# B293A_CoX_Amp_with_Programmable_Gain.net
KiCad netlist of a schematic drawn in Altium Designer
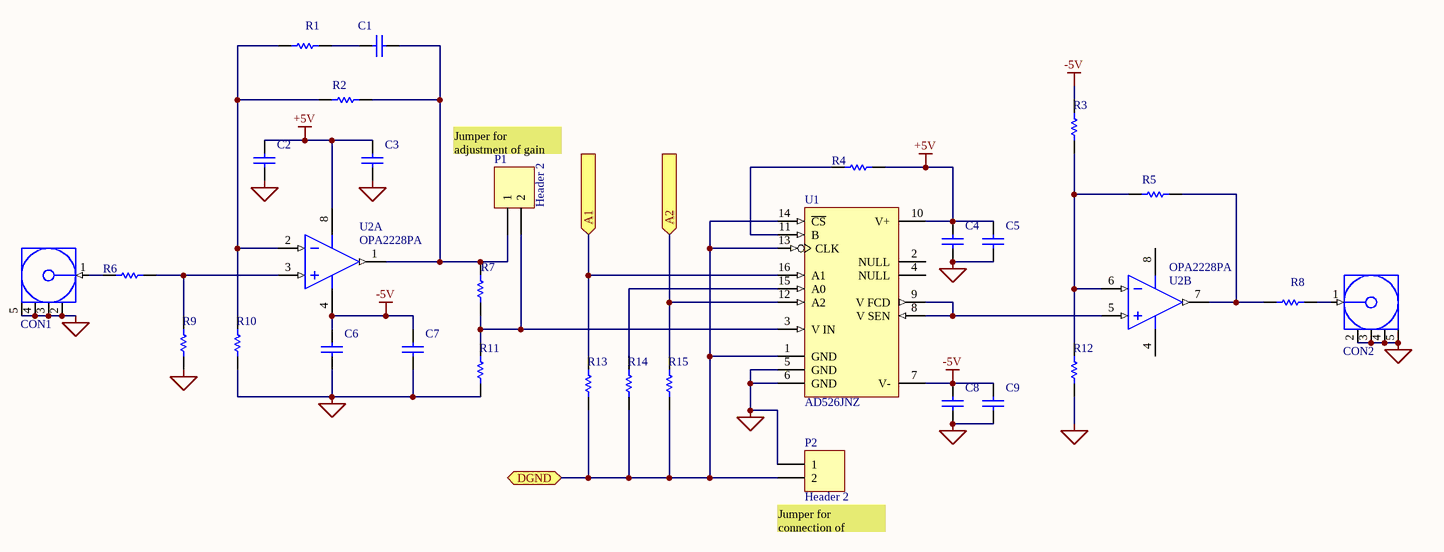
[diagram p0: B293A CoX Amp with Programmable Gain.SchDoc]

(export (version "E")
  (design (tool "Eeschema 10.0.6"))
  (components
    (comp (ref "C1")
      (value "CAP 47pF 50V 1206(3216)")
      (footprint "CAPC1206(3216)170_M")
      (description "CAP 47pF 50V ±10% 1206 (3216 Metric) Thickness 1.7mm SMD")
      (fields (field (name "TOLERANCE") "±10%"))
      (libsource (lib "Altium Content Vault") (part "CAP"))
    )
    (comp (ref "C2")
      (value "CAP 10uF 50V 1206(3216)")
      (footprint "CAPC1206(3216)190_M")
      (description "CAP 10uF 50V ±10% 1206 (3216 Metric) Thickness 1.9mm SMD")
      (fields (field (name "TOLERANCE") "±10%"))
      (libsource (lib "Altium Content Vault") (part "CAP"))
    )
    (comp (ref "C3")
      (value "CAP 10nF 50V 1206(3216)")
      (footprint "CAPC1206(3216)170_M")
      (description "CAP 10nF 50V ±10% 1206 (3216 Metric) Thickness 1.7mm SMD")
      (fields (field (name "TOLERANCE") "±10%"))
      (libsource (lib "Altium Content Vault") (part "CAP"))
    )
    (comp (ref "C4")
      (value "CAP 10nF 50V 1206(3216)")
      (footprint "CAPC1206(3216)170_M")
      (description "CAP 10nF 50V ±10% 1206 (3216 Metric) Thickness 1.7mm SMD")
      (fields (field (name "TOLERANCE") "±10%"))
      (libsource (lib "Altium Content Vault") (part "CAP"))
    )
    (comp (ref "C5")
      (value "CAP 10uF 50V 1206(3216)")
      (footprint "CAPC1206(3216)190_M")
      (description "CAP 10uF 50V ±10% 1206 (3216 Metric) Thickness 1.9mm SMD")
      (fields (field (name "TOLERANCE") "±10%"))
      (libsource (lib "Altium Content Vault") (part "CAP"))
    )
    (comp (ref "C6")
      (value "CAP 10nF 50V 1206(3216)")
      (footprint "CAPC1206(3216)170_M")
      (description "CAP 10nF 50V ±10% 1206 (3216 Metric) Thickness 1.7mm SMD")
      (fields (field (name "TOLERANCE") "±10%"))
      (libsource (lib "Altium Content Vault") (part "CAP"))
    )
    (comp (ref "C7")
      (value "CAP 10uF 50V 1206(3216)")
      (footprint "CAPC1206(3216)190_M")
      (description "CAP 10uF 50V ±10% 1206 (3216 Metric) Thickness 1.9mm SMD")
      (fields (field (name "TOLERANCE") "±10%"))
      (libsource (lib "Altium Content Vault") (part "CAP"))
    )
    (comp (ref "C8")
      (value "CAP 10nF 50V 1206(3216)")
      (footprint "CAPC1206(3216)170_M")
      (description "CAP 10nF 50V ±10% 1206 (3216 Metric) Thickness 1.7mm SMD")
      (fields (field (name "TOLERANCE") "±10%"))
      (libsource (lib "Altium Content Vault") (part "CAP"))
    )
    (comp (ref "C9")
      (value "CAP 10uF 50V 1206(3216)")
      (footprint "CAPC1206(3216)190_M")
      (description "CAP 10uF 50V ±10% 1206 (3216 Metric) Thickness 1.9mm SMD")
      (fields (field (name "TOLERANCE") "±10%"))
      (libsource (lib "Altium Content Vault") (part "CAP"))
    )
    (comp (ref "CON1")
      (value "SMA Vertical")
      (footprint "Matt PCB Library:SMA Vertical")
      (fields (field (name "MANUFACTURERS PART NO") "5-1814832-1"))
      (libsource (lib "Matt SCH Library") (part "SMA Vertical"))
    )
    (comp (ref "CON2")
      (value "SMA Vertical")
      (footprint "Matt PCB Library:SMA Vertical")
      (fields (field (name "MANUFACTURERS PART NO") "5-1814832-1"))
      (libsource (lib "Matt SCH Library") (part "SMA Vertical"))
    )
    (comp (ref "P1")
      (value "Header 2")
      (footprint "HDR1X2")
      (description "Header, 2-Pin")
      (fields (field (name "PUBLISHER") "Altium Limited"))
      (libsource (lib "") (part "Header 2_1"))
    )
    (comp (ref "P2")
      (value "Header 2")
      (footprint "HDR1X2")
      (description "Header, 2-Pin")
      (fields (field (name "PUBLISHER") "Altium Limited"))
      (libsource (lib "Miscellaneous Connectors") (part "Header 2"))
    )
    (comp (ref "R1")
      (value "1K5 1% 1206(3216)")
      (footprint "RESC1206(3216)_L")
      (description "1K5 0.25W 1% 1206 (3216 Metric)  SMD")
      (fields (field (name "TOLERANCE") "1 %"))
      (libsource (lib "Altium Content Vault") (part "RES"))
    )
    (comp (ref "R2")
      (value "100K 1% 1206(3216)")
      (footprint "RESC1206(3216)_L")
      (description "100K 0.25W 1% 1206 (3216 Metric)  SMD")
      (fields (field (name "TOLERANCE") "1 %"))
      (libsource (lib "Altium Content Vault") (part "RES"))
    )
    (comp (ref "R3")
      (value "150K 1% 1206(3216)")
      (footprint "RESC1206(3216)_L")
      (description "150K 0.25W 1% 1206 (3216 Metric)  SMD")
      (fields (field (name "TOLERANCE") "1 %"))
      (libsource (lib "Altium Content Vault") (part "RES"))
    )
    (comp (ref "R4")
      (value "10K 1% 1206(3216)")
      (footprint "RESC1206(3216)_L")
      (description "10K 0.25W 1% 1206 (3216 Metric)  SMD")
      (fields (field (name "TOLERANCE") "1 %"))
      (libsource (lib "Altium Content Vault") (part "RES"))
    )
    (comp (ref "R5")
      (value "10K 1% 1206(3216)")
      (footprint "RESC1206(3216)_L")
      (description "10K 0.25W 1% 1206 (3216 Metric)  SMD")
      (fields (field (name "TOLERANCE") "1 %"))
      (libsource (lib "Altium Content Vault") (part "RES"))
    )
    (comp (ref "R6")
      (value "100R 1% 1206(3216)")
      (footprint "RESC1206(3216)_N")
      (description "100R 0.25W 1% 1206 (3216 Metric)  SMD")
      (fields (field (name "TOLERANCE") "1 %"))
      (libsource (lib "Altium Content Vault") (part "RES"))
    )
    (comp (ref "R7")
      (value "10K 1% 1206(3216)")
      (footprint "RESC1206(3216)_L")
      (description "10K 0.25W 1% 1206 (3216 Metric)  SMD")
      (fields (field (name "TOLERANCE") "1 %"))
      (libsource (lib "Altium Content Vault") (part "RES"))
    )
    (comp (ref "R8")
      (value "100R 1% 1206(3216)")
      (footprint "RESC1206(3216)_N")
      (description "100R 0.25W 1% 1206 (3216 Metric)  SMD")
      (fields (field (name "TOLERANCE") "1 %"))
      (libsource (lib "Altium Content Vault") (part "RES"))
    )
    (comp (ref "R9")
      (value "27K 1% 1206(3216)")
      (footprint "RESC1206(3216)_M")
      (description "27K 0.25W 1% 1206 (3216 Metric)  SMD")
      (fields (field (name "TOLERANCE") "1 %"))
      (libsource (lib "Altium Content Vault") (part "RES"))
    )
    (comp (ref "R10")
      (value "330R 1% 1206(3216)")
      (footprint "RESC1206(3216)_M")
      (description "330R 0.25W 1% 1206 (3216 Metric)  SMD")
      (fields (field (name "TOLERANCE") "1 %"))
      (libsource (lib "Altium Content Vault") (part "RES"))
    )
    (comp (ref "R11")
      (value "1K2 1% 1206(3216)")
      (footprint "RESC1206(3216)_M")
      (description "1K2 0.25W 1% 1206 (3216 Metric)  SMD")
      (fields (field (name "TOLERANCE") "1 %"))
      (libsource (lib "Altium Content Vault") (part "CMP-1014-00518-1"))
    )
    (comp (ref "R12")
      (value "1K2 1% 1206(3216)")
      (footprint "RESC1206(3216)_M")
      (description "1K2 0.25W 1% 1206 (3216 Metric)  SMD")
      (fields (field (name "TOLERANCE") "1 %"))
      (libsource (lib "Altium Content Vault") (part "RES"))
    )
    (comp (ref "R13")
      (value "10K 1% 1206(3216)")
      (footprint "RESC1206(3216)_L")
      (description "10K 0.25W 1% 1206 (3216 Metric)  SMD")
      (fields (field (name "TOLERANCE") "1 %"))
      (libsource (lib "Altium Content Vault") (part "RES"))
    )
    (comp (ref "R14")
      (value "10K 1% 1206(3216)")
      (footprint "RESC1206(3216)_L")
      (description "10K 0.25W 1% 1206 (3216 Metric)  SMD")
      (fields (field (name "TOLERANCE") "1 %"))
      (libsource (lib "Altium Content Vault") (part "RES"))
    )
    (comp (ref "R15")
      (value "10K 1% 1206(3216)")
      (footprint "RESC1206(3216)_L")
      (description "10K 0.25W 1% 1206 (3216 Metric)  SMD")
      (fields (field (name "TOLERANCE") "1 %"))
      (libsource (lib "Altium Content Vault") (part "RES"))
    )
    (comp (ref "U1")
      (value "AD526JNZ")
      (footprint "D-16_B")
      (description "Software Programmable Gain Amplifier")
      (fields (field (name "PUBLISHER") "Altium Limited"))
      (libsource (lib "AD Instrumentation Amplifier") (part "AD526AD"))
    )
    (comp (ref "U2")
      (value "OPA2228PA")
      (footprint "TI-P8")
      (fields (field (name "MANUFACTURER") "Texas Instruments"))
      (libsource (lib "Altium Content Vault") (part "TI-OPA-8_2"))
    )
  )
  (nets
    (net (code "1") (name "+5V") (class "Default")
      (node (ref "C2") (pin "2") (pinfunction "2_2") (pintype "passive"))
      (node (ref "C3") (pin "2") (pinfunction "2_2") (pintype "passive"))
      (node (ref "C4") (pin "2") (pinfunction "2_2") (pintype "passive"))
      (node (ref "C5") (pin "2") (pinfunction "2_2") (pintype "passive"))
      (node (ref "R4") (pin "1") (pinfunction "1_1") (pintype "passive"))
      (node (ref "U1") (pin "10") (pinfunction "V+_10") (pintype "power_in"))
      (node (ref "U2") (pin "8") (pinfunction "V+_8") (pintype "power_in"))
    )
    (net (code "2") (name "-5V") (class "Default")
      (node (ref "C6") (pin "2") (pinfunction "2_2") (pintype "passive"))
      (node (ref "C7") (pin "2") (pinfunction "2_2") (pintype "passive"))
      (node (ref "C8") (pin "2") (pinfunction "2_2") (pintype "passive"))
      (node (ref "C9") (pin "2") (pinfunction "2_2") (pintype "passive"))
      (node (ref "R3") (pin "2") (pinfunction "2_2") (pintype "passive"))
      (node (ref "U1") (pin "7") (pinfunction "V-_7") (pintype "power_in"))
      (node (ref "U2") (pin "4") (pinfunction "V-_4") (pintype "power_in"))
    )
    (net (code "3") (name "/A1") (class "Default")
      (node (ref "R13") (pin "2") (pinfunction "2_2") (pintype "passive"))
      (node (ref "U1") (pin "16") (pinfunction "A1_16") (pintype "input"))
    )
    (net (code "4") (name "/A2") (class "Default")
      (node (ref "R15") (pin "2") (pinfunction "2_2") (pintype "passive"))
      (node (ref "U1") (pin "12") (pinfunction "A2_12") (pintype "input"))
    )
    (net (code "5") (name "/DGND") (class "Default")
      (node (ref "P2") (pin "2") (pinfunction "2_2") (pintype "passive"))
      (node (ref "R13") (pin "1") (pinfunction "1_1") (pintype "passive"))
      (node (ref "R14") (pin "1") (pinfunction "1_1") (pintype "passive"))
      (node (ref "R15") (pin "1") (pinfunction "1_1") (pintype "passive"))
      (node (ref "U1") (pin "1") (pinfunction "GND_1") (pintype "power_in"))
      (node (ref "U1") (pin "13") (pinfunction "CLK_13") (pintype "input"))
      (node (ref "U1") (pin "14") (pinfunction "~{CS}_14") (pintype "input"))
    )
    (net (code "6") (name "GND") (class "Default")
      (node (ref "C2") (pin "1") (pinfunction "1_1") (pintype "passive"))
      (node (ref "C3") (pin "1") (pinfunction "1_1") (pintype "passive"))
      (node (ref "C4") (pin "1") (pinfunction "1_1") (pintype "passive"))
      (node (ref "C5") (pin "1") (pinfunction "1_1") (pintype "passive"))
      (node (ref "C6") (pin "1") (pinfunction "1_1") (pintype "passive"))
      (node (ref "C7") (pin "1") (pinfunction "1_1") (pintype "passive"))
      (node (ref "C8") (pin "1") (pinfunction "1_1") (pintype "passive"))
      (node (ref "C9") (pin "1") (pinfunction "1_1") (pintype "passive"))
      (node (ref "CON1") (pin "2") (pinfunction "GND_2") (pintype "power_in"))
      (node (ref "CON1") (pin "3") (pinfunction "GND_3") (pintype "power_in"))
      (node (ref "CON1") (pin "4") (pinfunction "GND_4") (pintype "power_in"))
      (node (ref "CON1") (pin "5") (pinfunction "GND_5") (pintype "power_in"))
      (node (ref "CON2") (pin "2") (pinfunction "GND_2") (pintype "power_in"))
      (node (ref "CON2") (pin "3") (pinfunction "GND_3") (pintype "power_in"))
      (node (ref "CON2") (pin "4") (pinfunction "GND_4") (pintype "power_in"))
      (node (ref "CON2") (pin "5") (pinfunction "GND_5") (pintype "power_in"))
      (node (ref "P2") (pin "1") (pinfunction "1_1") (pintype "passive"))
      (node (ref "R10") (pin "1") (pinfunction "1_1") (pintype "passive"))
      (node (ref "R11") (pin "1") (pinfunction "1_1") (pintype "passive"))
      (node (ref "R12") (pin "1") (pinfunction "1_1") (pintype "passive"))
      (node (ref "R9") (pin "1") (pinfunction "1_1") (pintype "passive"))
      (node (ref "U1") (pin "5") (pinfunction "GND_5") (pintype "power_in"))
      (node (ref "U1") (pin "6") (pinfunction "GND_6") (pintype "power_in"))
    )
    (net (code "7") (name "Net-(C1-Pad2)") (class "Default")
      (node (ref "C1") (pin "2") (pinfunction "2_2") (pintype "passive"))
      (node (ref "R1") (pin "2") (pinfunction "2_2") (pintype "passive"))
    )
    (net (code "8") (name "Net-(CON1-Signal)") (class "Default")
      (node (ref "CON1") (pin "1") (pinfunction "Signal_1") (pintype "input"))
      (node (ref "R6") (pin "2") (pinfunction "2_2") (pintype "passive"))
    )
    (net (code "9") (name "Net-(CON2-Signal)") (class "Default")
      (node (ref "CON2") (pin "1") (pinfunction "Signal_1") (pintype "input"))
      (node (ref "R8") (pin "2") (pinfunction "2_2") (pintype "passive"))
    )
    (net (code "10") (name "Net-(U1-A0)") (class "Default")
      (node (ref "R14") (pin "2") (pinfunction "2_2") (pintype "passive"))
      (node (ref "U1") (pin "15") (pinfunction "A0_15") (pintype "input"))
    )
    (net (code "11") (name "Net-(U1-B)") (class "Default")
      (node (ref "R4") (pin "2") (pinfunction "2_2") (pintype "passive"))
      (node (ref "U1") (pin "11") (pinfunction "B_11") (pintype "input"))
    )
    (net (code "12") (name "Net-(U1-V_FCD)") (class "Default")
      (node (ref "U1") (pin "8") (pinfunction "V_SEN_8") (pintype "input"))
      (node (ref "U1") (pin "9") (pinfunction "V_FCD_9") (pintype "output"))
      (node (ref "U2") (pin "5") (pinfunction "IN_B+_5") (pintype "input"))
    )
    (net (code "13") (name "Net-(U1-V_IN)") (class "Default")
      (node (ref "P1") (pin "2") (pinfunction "2_2") (pintype "passive"))
      (node (ref "R11") (pin "2") (pinfunction "2_2") (pintype "passive"))
      (node (ref "R7") (pin "1") (pinfunction "1_1") (pintype "passive"))
      (node (ref "U1") (pin "3") (pinfunction "V_IN_3") (pintype "input"))
    )
    (net (code "14") (name "Net-(U2A-IN_A+)") (class "Default")
      (node (ref "R6") (pin "1") (pinfunction "1_1") (pintype "passive"))
      (node (ref "R9") (pin "2") (pinfunction "2_2") (pintype "passive"))
      (node (ref "U2") (pin "3") (pinfunction "IN_A+_3") (pintype "input"))
    )
    (net (code "15") (name "Net-(U2A-IN_A-)") (class "Default")
      (node (ref "R1") (pin "1") (pinfunction "1_1") (pintype "passive"))
      (node (ref "R10") (pin "2") (pinfunction "2_2") (pintype "passive"))
      (node (ref "R2") (pin "1") (pinfunction "1_1") (pintype "passive"))
      (node (ref "U2") (pin "2") (pinfunction "IN_A-_2") (pintype "input"))
    )
    (net (code "16") (name "Net-(U2A-OUT_A)") (class "Default")
      (node (ref "C1") (pin "1") (pinfunction "1_1") (pintype "passive"))
      (node (ref "P1") (pin "1") (pinfunction "1_1") (pintype "passive"))
      (node (ref "R2") (pin "2") (pinfunction "2_2") (pintype "passive"))
      (node (ref "R7") (pin "2") (pinfunction "2_2") (pintype "passive"))
      (node (ref "U2") (pin "1") (pinfunction "OUT_A_1") (pintype "output"))
    )
    (net (code "17") (name "Net-(U2B-IN_B-)") (class "Default")
      (node (ref "R12") (pin "2") (pinfunction "2_2") (pintype "passive"))
      (node (ref "R3") (pin "1") (pinfunction "1_1") (pintype "passive"))
      (node (ref "R5") (pin "1") (pinfunction "1_1") (pintype "passive"))
      (node (ref "U2") (pin "6") (pinfunction "IN_B-_6") (pintype "input"))
    )
    (net (code "18") (name "Net-(U2B-OUT_B)") (class "Default")
      (node (ref "R5") (pin "2") (pinfunction "2_2") (pintype "passive"))
      (node (ref "R8") (pin "1") (pinfunction "1_1") (pintype "passive"))
      (node (ref "U2") (pin "7") (pinfunction "OUT_B_7") (pintype "output"))
    )
    (net (code "19") (name "unconnected-(U1-NULL-Pad2)") (class "Default")
      (node (ref "U1") (pin "2") (pinfunction "NULL_2") (pintype "passive"))
    )
    (net (code "20") (name "unconnected-(U1-NULL-Pad4)") (class "Default")
      (node (ref "U1") (pin "4") (pinfunction "NULL_4") (pintype "passive"))
    )
    (net (code "21") (name "unconnected-(U2B-V+-Pad8)") (class "Default")
      (node (ref "U2") (pin "8") (pinfunction "V+_8") (pintype "power_in"))
    )
    (net (code "22") (name "unconnected-(U2B-V--Pad4)") (class "Default")
      (node (ref "U2") (pin "4") (pinfunction "V-_4") (pintype "power_in"))
    )
  )
)
